# Przeka_nik_A4_Landscape.net
KiCad netlist of a schematic drawn in Altium Designer
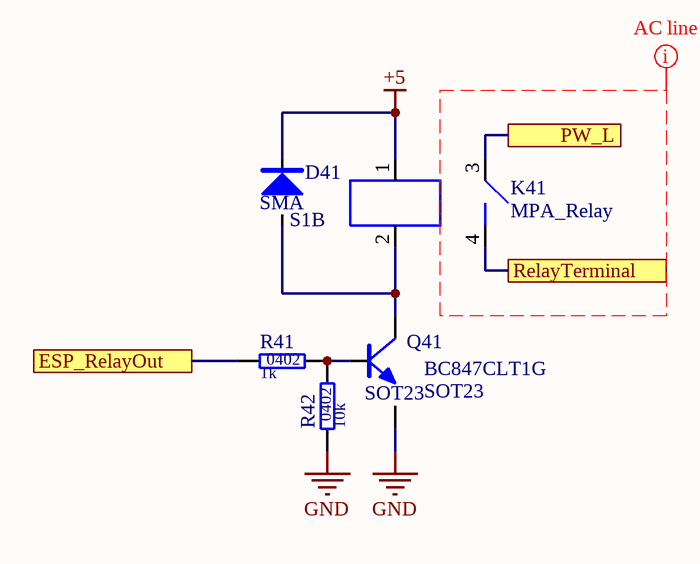
[diagram p0: Przekaźnik_A4_Landscape_.SchDoc]

(export (version "E")
  (design (tool "Eeschema 10.0.6"))
  (components
    (comp (ref "D41")
      (value "S1B")
      (footprint "SMA_DO-214AC")
      (fields
        (field (name "SCH_FOOTPRINT") "SMA")
        (field (name "PART NUMBER") "D_S1B_1A_100V_SMA")
        (field (name "VOLTAGE") "100V")
        (field (name "MANUFACTURER") "Vishay/General Semiconductor")
      )
      (libsource (lib "Library") (part "D"))
    )
    (comp (ref "K41")
      (value "MPA_Relay")
      (footprint "MPA_Relay")
      (libsource (lib "Integrated_Library1") (part "MPA_Relay"))
    )
    (comp (ref "Q41")
      (value "BC847CLT1G")
      (footprint "SOT23_TO236_SC59")
      (fields
        (field (name "PART NUMBER") "QNP_BC847C_45V_0A1")
        (field (name "SCH_FOOTPRINT") "SOT23")
        (field (name "VOLTAGE") "45V")
        (field (name "MANUFACTURER") "ON Semiconductor")
      )
      (libsource (lib "Library") (part "QNP_BEC"))
    )
    (comp (ref "R41")
      (value "1k")
      (footprint "R_0402_1005")
      (fields
        (field (name "SCH_FOOTPRINT") "0402")
        (field (name "PART NUMBER") "R_1k_0402")
        (field (name "VOLTAGE") "50V")
        (field (name "POWER") "63mW")
      )
      (libsource (lib "Library") (part "R"))
    )
    (comp (ref "R42")
      (value "10k")
      (footprint "R_0402_1005")
      (fields
        (field (name "SCH_FOOTPRINT") "0402")
        (field (name "PART NUMBER") "R_10k_0402_1")
        (field (name "VOLTAGE") "50V")
        (field (name "POWER") "63mW")
      )
      (libsource (lib "Library") (part "R"))
    )
  )
  (nets
    (net (code "1") (name "+5") (class "Default")
      (node (ref "D41") (pin "1") (pintype "passive"))
      (node (ref "K41") (pin "1") (pinfunction "0_1") (pintype "passive"))
    )
    (net (code "2") (name "/ESP_RelayOut") (class "Default")
      (node (ref "R41") (pin "1") (pinfunction "1_1") (pintype "passive"))
    )
    (net (code "3") (name "/PW_L") (class "Default")
      (node (ref "K41") (pin "3") (pinfunction "3_3") (pintype "passive"))
    )
    (net (code "4") (name "/RelayTerminal") (class "Default")
      (node (ref "K41") (pin "4") (pinfunction "4_4") (pintype "passive"))
    )
    (net (code "5") (name "GND") (class "Default")
      (node (ref "Q41") (pin "2") (pinfunction "E_2") (pintype "passive"))
      (node (ref "R42") (pin "1") (pinfunction "1_1") (pintype "passive"))
    )
    (net (code "6") (name "Net-(K41-1)") (class "Default")
      (node (ref "D41") (pin "2") (pintype "passive"))
      (node (ref "K41") (pin "2") (pinfunction "1_2") (pintype "passive"))
      (node (ref "Q41") (pin "3") (pinfunction "C_3") (pintype "passive"))
    )
    (net (code "7") (name "Net-(Q41-B)") (class "Default")
      (node (ref "Q41") (pin "1") (pinfunction "B_1") (pintype "passive"))
      (node (ref "R41") (pin "2") (pinfunction "2_2") (pintype "passive"))
      (node (ref "R42") (pin "2") (pinfunction "2_2") (pintype "passive"))
    )
  )
)
